# Adafruit_LSM6DS3.net
KiCad netlist of a schematic drawn in EAGLE
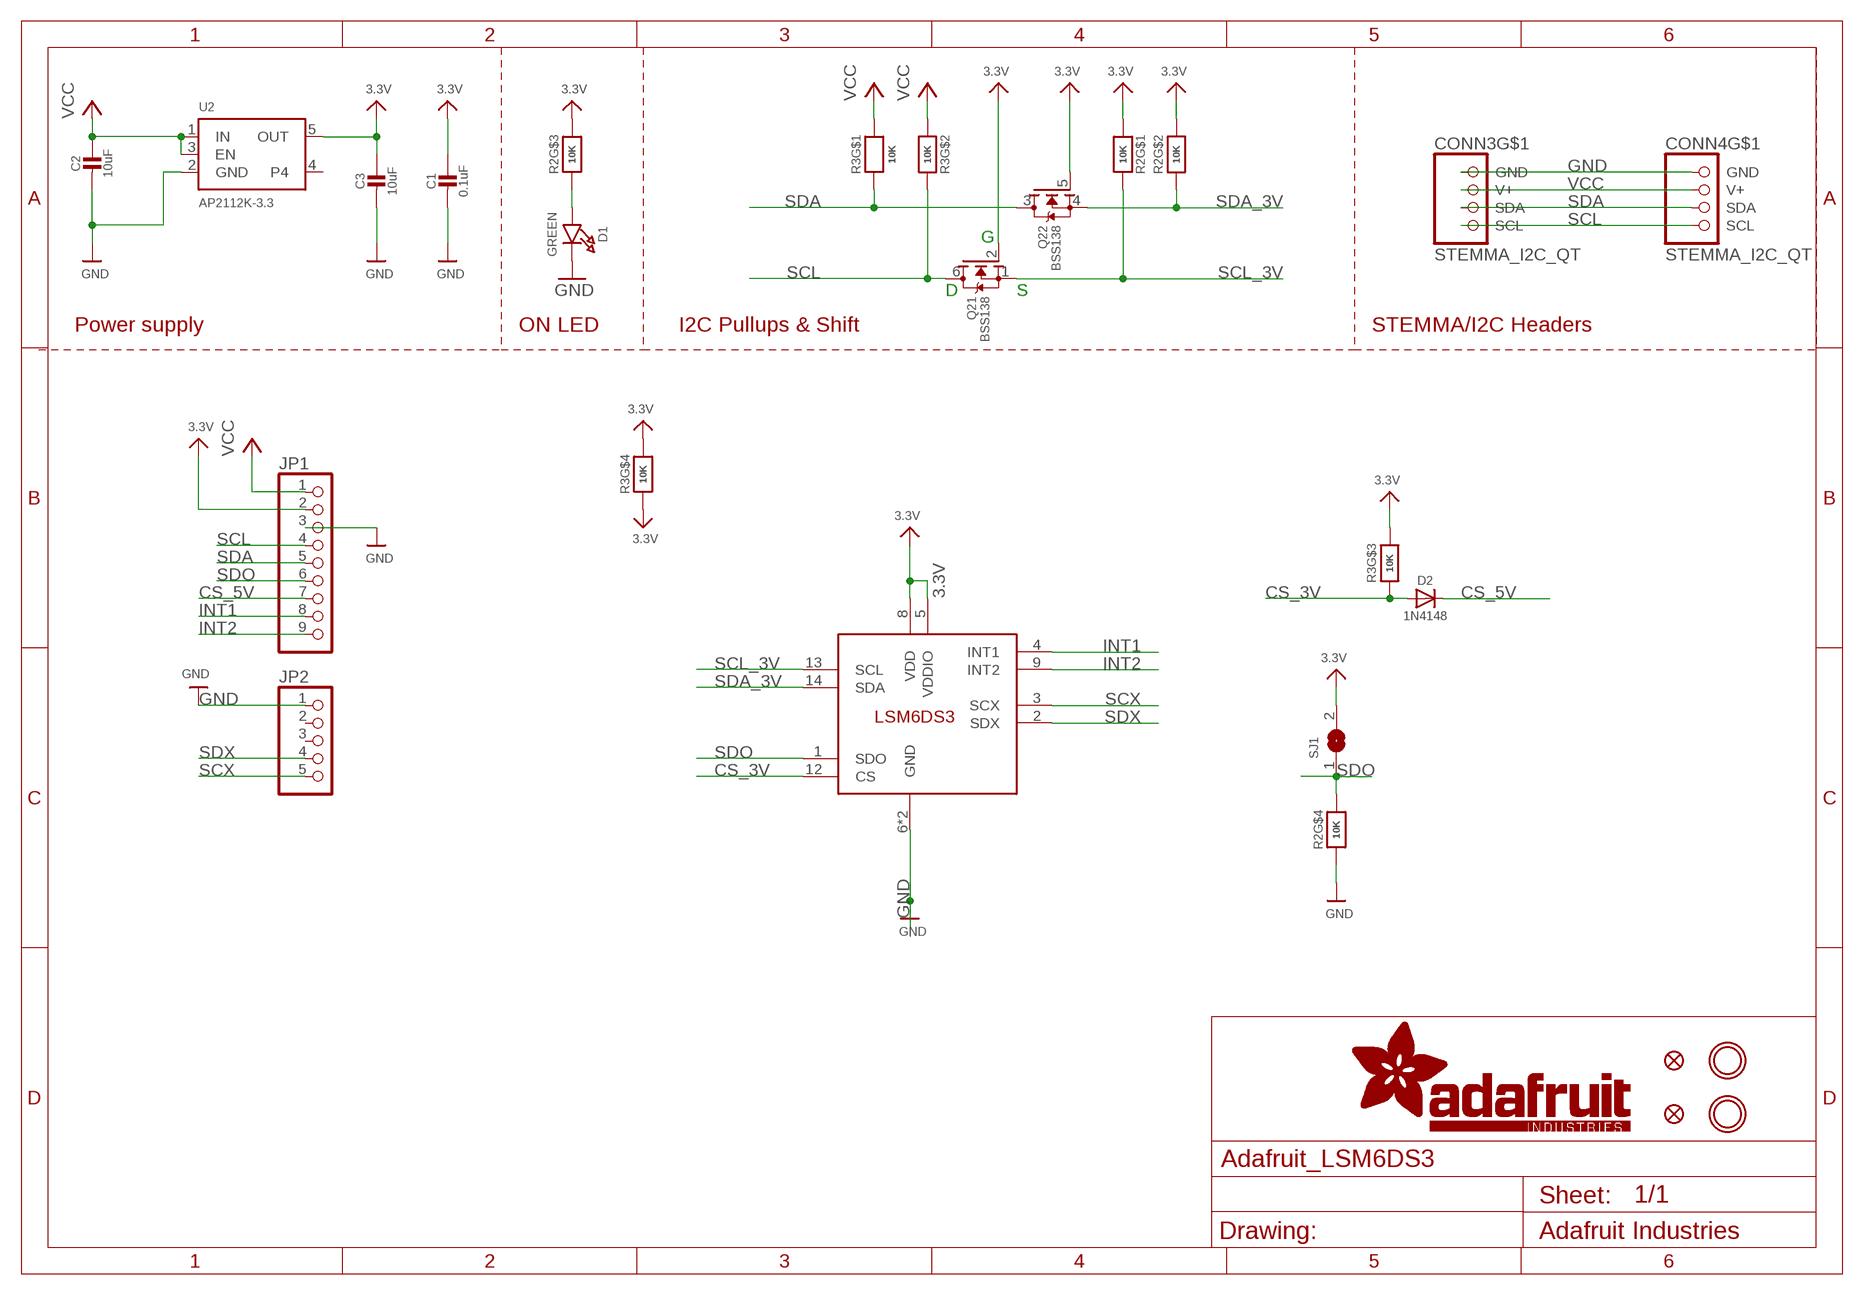
[diagram p0: schematic, sheet 1]

(export (version "E")
  (design (tool "Eeschema 10.0.6"))
  (components
    (comp (ref "C1")
      (value "0.1uF")
      (footprint "eagle-import:0603-NO")
      (libsource (lib "eagle-import") (part "CAP_CERAMIC0603_NO"))
    )
    (comp (ref "C2")
      (value "10uF")
      (footprint "eagle-import:0805-NO")
      (libsource (lib "eagle-import") (part "CAP_CERAMIC0805-NOOUTLINE"))
    )
    (comp (ref "C3")
      (value "10uF")
      (footprint "eagle-import:0805-NO")
      (libsource (lib "eagle-import") (part "CAP_CERAMIC0805-NOOUTLINE"))
    )
    (comp (ref "CONN3")
      (value "STEMMA_I2C_QT")
      (footprint "eagle-import:JST_SH4")
      (libsource (lib "eagle-import") (part "STEMMA_I2C_QT"))
    )
    (comp (ref "CONN4")
      (value "STEMMA_I2C_QT")
      (footprint "eagle-import:JST_SH4")
      (libsource (lib "eagle-import") (part "STEMMA_I2C_QT"))
    )
    (comp (ref "D1")
      (value "GREEN")
      (footprint "eagle-import:CHIPLED_0603_NOOUTLINE")
      (libsource (lib "eagle-import") (part "LED0603_NOOUTLINE"))
    )
    (comp (ref "D2")
      (value "1N4148")
      (footprint "eagle-import:SOD-323")
      (libsource (lib "eagle-import") (part "DIODESOD-323"))
    )
    (comp (ref "FID3")
      (value "FIDUCIAL_1MM")
      (footprint "eagle-import:FIDUCIAL_1MM")
      (libsource (lib "eagle-import") (part "FIDUCIAL_1MM"))
    )
    (comp (ref "FID4")
      (value "FIDUCIAL_1MM")
      (footprint "eagle-import:FIDUCIAL_1MM")
      (libsource (lib "eagle-import") (part "FIDUCIAL_1MM"))
    )
    (comp (ref "JP1")
      (value "HEADER-1X970MIL")
      (footprint "eagle-import:1X09_ROUND_70")
      (libsource (lib "eagle-import") (part "HEADER-1X970MIL"))
    )
    (comp (ref "JP2")
      (value "HEADER-1X570MIL")
      (footprint "eagle-import:1X05_ROUND_70")
      (libsource (lib "eagle-import") (part "HEADER-1X570MIL"))
    )
    (comp (ref "Q2")
      (value "BSS138")
      (footprint "eagle-import:SOT363")
      (libsource (lib "eagle-import") (part "MOSFET-N_DUAL"))
    )
    (comp (ref "R2")
      (value "10K")
      (footprint "eagle-import:RESPACK_4X0603")
      (libsource (lib "eagle-import") (part "RESISTOR_4PACK"))
    )
    (comp (ref "R3")
      (value "10K")
      (footprint "eagle-import:RESPACK_4X0603")
      (libsource (lib "eagle-import") (part "RESISTOR_4PACK"))
    )
    (comp (ref "SJ1")
      (value "SOLDERJUMPER")
      (footprint "eagle-import:SOLDERJUMPER_ARROW_NOPASTE")
      (libsource (lib "eagle-import") (part "SOLDERJUMPER"))
    )
    (comp (ref "U$1")
      (value "MOUNTINGHOLE2.5")
      (footprint "eagle-import:MOUNTINGHOLE_2.5_PLATED")
      (libsource (lib "eagle-import") (part "MOUNTINGHOLE2.5"))
    )
    (comp (ref "U$17")
      (value "MOUNTINGHOLE2.5")
      (footprint "eagle-import:MOUNTINGHOLE_2.5_PLATED")
      (libsource (lib "eagle-import") (part "MOUNTINGHOLE2.5"))
    )
    (comp (ref "U1")
      (value "LSM6DS3")
      (footprint "eagle-import:LGA-14L")
      (libsource (lib "eagle-import") (part "LSM6DS3"))
    )
    (comp (ref "U2")
      (value "AP2112K-3.3")
      (footprint "eagle-import:SOT23-5")
      (libsource (lib "eagle-import") (part "VREG_SOT23-5"))
    )
  )
  (nets
    (net (code "1") (name "/CS_3V") (class "Default")
      (node (ref "D2") (pin "A") (pinfunction "A_A") (pintype "passive"))
      (node (ref "R3") (pin "6") (pinfunction "2_6") (pintype "passive"))
      (node (ref "U1") (pin "12") (pinfunction "CS_12") (pintype "bidirectional"))
    )
    (net (code "2") (name "/CS_5V") (class "Default")
      (node (ref "D2") (pin "C") (pinfunction "C_C") (pintype "passive"))
      (node (ref "JP1") (pin "7") (pinfunction "7_7") (pintype "passive"))
    )
    (net (code "3") (name "/INT1") (class "Default")
      (node (ref "JP1") (pin "8") (pinfunction "8_8") (pintype "passive"))
      (node (ref "U1") (pin "4") (pinfunction "INT1_4") (pintype "bidirectional"))
    )
    (net (code "4") (name "/INT2") (class "Default")
      (node (ref "JP1") (pin "9") (pinfunction "9_9") (pintype "passive"))
      (node (ref "U1") (pin "9") (pinfunction "INT2_9") (pintype "bidirectional"))
    )
    (net (code "5") (name "/SCL") (class "Default")
      (node (ref "CONN3") (pin "4") (pinfunction "SCL_4") (pintype "passive"))
      (node (ref "CONN4") (pin "4") (pinfunction "SCL_4") (pintype "passive"))
      (node (ref "JP1") (pin "4") (pinfunction "4_4") (pintype "passive"))
      (node (ref "Q2") (pin "6") (pinfunction "D_6") (pintype "bidirectional"))
      (node (ref "R3") (pin "2") (pinfunction "1_2") (pintype "passive"))
    )
    (net (code "6") (name "/SCL_3V") (class "Default")
      (node (ref "Q2") (pin "1") (pinfunction "S_1") (pintype "bidirectional"))
      (node (ref "R2") (pin "8") (pinfunction "2_8") (pintype "passive"))
      (node (ref "U1") (pin "13") (pinfunction "SCL_13") (pintype "bidirectional"))
    )
    (net (code "7") (name "/SCX") (class "Default")
      (node (ref "JP2") (pin "5") (pinfunction "5_5") (pintype "passive"))
      (node (ref "U1") (pin "3") (pinfunction "SCX_3") (pintype "bidirectional"))
    )
    (net (code "8") (name "/SDA") (class "Default")
      (node (ref "CONN3") (pin "3") (pinfunction "SDA_3") (pintype "passive"))
      (node (ref "CONN4") (pin "3") (pinfunction "SDA_3") (pintype "passive"))
      (node (ref "JP1") (pin "5") (pinfunction "5_5") (pintype "passive"))
      (node (ref "Q2") (pin "3") (pinfunction "D_3") (pintype "bidirectional"))
      (node (ref "R3") (pin "1") (pinfunction "1_1") (pintype "passive"))
    )
    (net (code "9") (name "/SDA_3V") (class "Default")
      (node (ref "Q2") (pin "4") (pinfunction "S_4") (pintype "bidirectional"))
      (node (ref "R2") (pin "7") (pinfunction "2_7") (pintype "passive"))
      (node (ref "U1") (pin "14") (pinfunction "SDA_14") (pintype "bidirectional"))
    )
    (net (code "10") (name "/SDO") (class "Default")
      (node (ref "JP1") (pin "6") (pinfunction "6_6") (pintype "passive"))
      (node (ref "R2") (pin "5") (pinfunction "2_5") (pintype "passive"))
      (node (ref "SJ1") (pin "1") (pinfunction "1_1") (pintype "passive"))
      (node (ref "U1") (pin "1") (pinfunction "SDO_1") (pintype "bidirectional"))
    )
    (net (code "11") (name "/SDX") (class "Default")
      (node (ref "JP2") (pin "4") (pinfunction "4_4") (pintype "passive"))
      (node (ref "U1") (pin "2") (pinfunction "SDX_2") (pintype "bidirectional"))
    )
    (net (code "12") (name "3.3V") (class "Default")
      (node (ref "C1") (pin "1") (pinfunction "1_1") (pintype "passive"))
      (node (ref "C3") (pin "1") (pinfunction "1_1") (pintype "passive"))
      (node (ref "JP1") (pin "2") (pinfunction "2_2") (pintype "passive"))
      (node (ref "Q2") (pin "2") (pinfunction "G_2") (pintype "bidirectional"))
      (node (ref "Q2") (pin "5") (pinfunction "G_5") (pintype "bidirectional"))
      (node (ref "R2") (pin "1") (pinfunction "1_1") (pintype "passive"))
      (node (ref "R2") (pin "2") (pinfunction "1_2") (pintype "passive"))
      (node (ref "R2") (pin "6") (pinfunction "2_6") (pintype "passive"))
      (node (ref "R3") (pin "3") (pinfunction "1_3") (pintype "passive"))
      (node (ref "R3") (pin "4") (pinfunction "1_4") (pintype "passive"))
      (node (ref "R3") (pin "5") (pinfunction "2_5") (pintype "passive"))
      (node (ref "SJ1") (pin "2") (pinfunction "2_2") (pintype "passive"))
      (node (ref "U1") (pin "5") (pinfunction "VDDIO_5") (pintype "power_in"))
      (node (ref "U1") (pin "8") (pinfunction "VDD_8") (pintype "power_in"))
      (node (ref "U2") (pin "5") (pinfunction "OUT_5") (pintype "power_in"))
    )
    (net (code "13") (name "GND") (class "Default")
      (node (ref "C1") (pin "2") (pinfunction "2_2") (pintype "passive"))
      (node (ref "C2") (pin "2") (pinfunction "2_2") (pintype "passive"))
      (node (ref "C3") (pin "2") (pinfunction "2_2") (pintype "passive"))
      (node (ref "CONN3") (pin "1") (pinfunction "GND_1") (pintype "passive"))
      (node (ref "CONN4") (pin "1") (pinfunction "GND_1") (pintype "passive"))
      (node (ref "D1") (pin "C") (pinfunction "C_C") (pintype "passive"))
      (node (ref "JP1") (pin "3") (pinfunction "3_3") (pintype "passive"))
      (node (ref "JP2") (pin "1") (pinfunction "1_1") (pintype "passive"))
      (node (ref "R2") (pin "4") (pinfunction "1_4") (pintype "passive"))
      (node (ref "U1") (pin "6") (pinfunction "GND_6") (pintype "power_in"))
      (node (ref "U1") (pin "7") (pinfunction "GND_7") (pintype "power_in"))
      (node (ref "U2") (pin "2") (pinfunction "GND_2") (pintype "power_in"))
    )
    (net (code "14") (name "Net-(R2C-1)") (class "Default")
      (node (ref "D1") (pin "A") (pinfunction "A_A") (pintype "passive"))
      (node (ref "R2") (pin "3") (pinfunction "1_3") (pintype "passive"))
    )
    (net (code "15") (name "VCC") (class "Default")
      (node (ref "C2") (pin "1") (pinfunction "1_1") (pintype "passive"))
      (node (ref "CONN3") (pin "2") (pinfunction "V+_2") (pintype "passive"))
      (node (ref "CONN4") (pin "2") (pinfunction "V+_2") (pintype "passive"))
      (node (ref "JP1") (pin "1") (pinfunction "1_1") (pintype "passive"))
      (node (ref "R3") (pin "7") (pinfunction "2_7") (pintype "passive"))
      (node (ref "R3") (pin "8") (pinfunction "2_8") (pintype "passive"))
      (node (ref "U2") (pin "1") (pinfunction "IN_1") (pintype "power_in"))
      (node (ref "U2") (pin "3") (pinfunction "EN_3") (pintype "input"))
    )
    (net (code "16") (name "unconnected-(JP2-Pad2)") (class "Default")
      (node (ref "JP2") (pin "2") (pinfunction "2_2") (pintype "passive"))
    )
    (net (code "17") (name "unconnected-(JP2-Pad3)") (class "Default")
      (node (ref "JP2") (pin "3") (pinfunction "3_3") (pintype "passive"))
    )
    (net (code "18") (name "unconnected-(U2-P4-Pad4)") (class "Default")
      (node (ref "U2") (pin "4") (pinfunction "P4_4") (pintype "bidirectional"))
    )
  )
)
